# HT7463A.net
KiCad netlist of a schematic drawn in Altium Designer
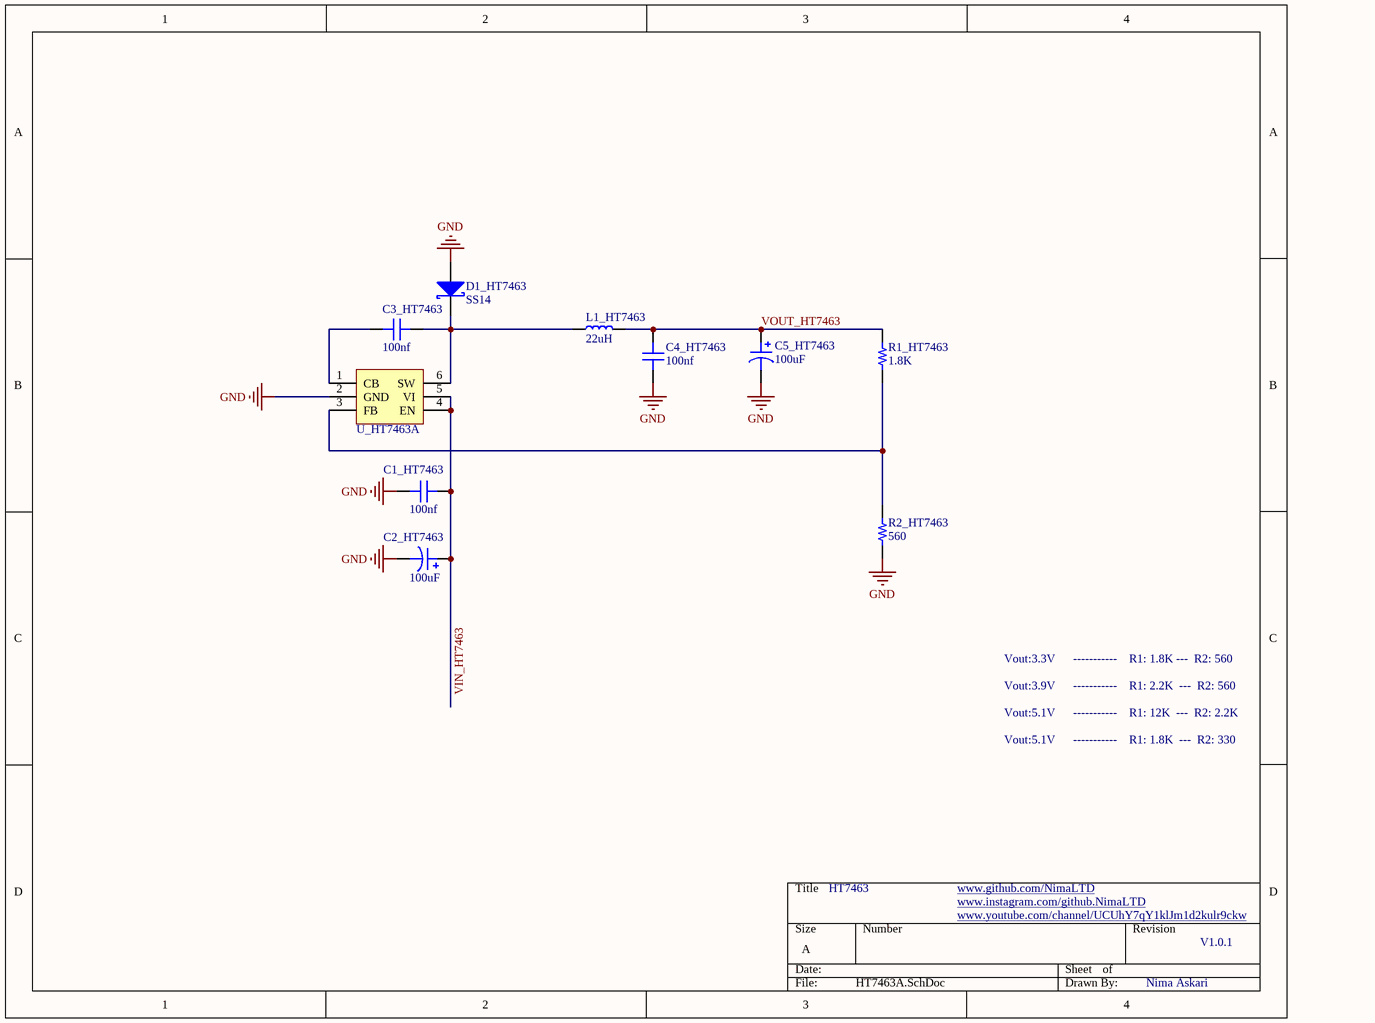
[diagram p0: HT7463A.SchDoc]

(export (version "E")
  (design (tool "Eeschema 10.0.6"))
  (components
    (comp (ref "C1_HT7463")
      (value "100nf")
      (footprint "CAP 1206")
      (description "SMT Capacitor")
      (libsource (lib "CAPACITOR") (part "Cap SMD 1206"))
    )
    (comp (ref "C2_HT7463")
      (value "100uF")
      (footprint "CAP AL SMD D6 H6")
      (description "SMT Polarised Capacitor")
      (libsource (lib "CAPACITOR") (part "Pol Cap SMD AL D6 H6"))
    )
    (comp (ref "C3_HT7463")
      (value "100nf")
      (footprint "CAP 0805")
      (description "SMT Capacitor")
      (libsource (lib "CAPACITOR") (part "Cap SMD 0805"))
    )
    (comp (ref "C4_HT7463")
      (value "100nf")
      (footprint "CAP 0805")
      (description "SMT Capacitor")
      (libsource (lib "CAPACITOR") (part "Cap SMD 0805"))
    )
    (comp (ref "C5_HT7463")
      (value "100uF")
      (footprint "CAP AL SMD D6 H6")
      (description "SMT Polarised Capacitor")
      (libsource (lib "") (part "Pol Cap SMD AL D6 H6_1"))
    )
    (comp (ref "D1_HT7463")
      (value "SS14 SMD")
      (footprint "DO214AC SMA")
      (description "1A Schottky")
      (fields (field (name "PARAMETER 1") "SS14"))
      (libsource (lib "DIODE") (part "SS14 SMD"))
    )
    (comp (ref "L1_HT7463")
      (value "22uH")
      (footprint "IND 5X5")
      (description "SMT Inductor")
      (fields (field (name "Comment") "Inductor SMD POWER 5X5mm"))
      (libsource (lib "INDUCTOR") (part "Inductor SMD POWER 5X5mm"))
    )
    (comp (ref "R1_HT7463")
      (value "1.8K")
      (footprint "RES 0805")
      (description "SMD Resistor")
      (libsource (lib "RESISTOR") (part "Res SMD 0805"))
    )
    (comp (ref "R2_HT7463")
      (value "560")
      (footprint "RES 0805")
      (description "SMD Resistor")
      (libsource (lib "RESISTOR") (part "Res SMD 0805"))
    )
    (comp (ref "U_HT7463A") (value "HT7463") (footprint "SOT23-6") (libsource (lib "IC") (part "HT7463")))
  )
  (nets
    (net (code "1") (name "/VIN_HT7463") (class "Default")
      (node (ref "C1_HT7463") (pin "2") (pinfunction "2_2") (pintype "passive"))
      (node (ref "C2_HT7463") (pin "1") (pinfunction "1_1") (pintype "passive"))
      (node (ref "U_HT7463A") (pin "4") (pinfunction "EN_4") (pintype "passive"))
      (node (ref "U_HT7463A") (pin "5") (pinfunction "VI_5") (pintype "passive"))
    )
    (net (code "2") (name "/VOUT_HT7463") (class "Default")
      (node (ref "C4_HT7463") (pin "2") (pinfunction "2_2") (pintype "passive"))
      (node (ref "C5_HT7463") (pin "1") (pinfunction "1_1") (pintype "passive"))
      (node (ref "L1_HT7463") (pin "2") (pinfunction "2_2") (pintype "passive"))
      (node (ref "R1_HT7463") (pin "2") (pinfunction "2_2") (pintype "passive"))
    )
    (net (code "3") (name "GND") (class "Default")
      (node (ref "C1_HT7463") (pin "1") (pinfunction "1_1") (pintype "passive"))
      (node (ref "C2_HT7463") (pin "2") (pinfunction "2_2") (pintype "passive"))
      (node (ref "C4_HT7463") (pin "1") (pinfunction "1_1") (pintype "passive"))
      (node (ref "C5_HT7463") (pin "2") (pinfunction "2_2") (pintype "passive"))
      (node (ref "D1_HT7463") (pin "1") (pinfunction "A_1") (pintype "passive"))
      (node (ref "R2_HT7463") (pin "1") (pinfunction "1_1") (pintype "passive"))
      (node (ref "U_HT7463A") (pin "2") (pinfunction "GND_2") (pintype "passive"))
    )
    (net (code "4") (name "Net-(D1_HT7463-K)") (class "Default")
      (node (ref "C3_HT7463") (pin "2") (pinfunction "2_2") (pintype "passive"))
      (node (ref "D1_HT7463") (pin "2") (pinfunction "K_2") (pintype "passive"))
      (node (ref "L1_HT7463") (pin "1") (pinfunction "1_1") (pintype "passive"))
      (node (ref "U_HT7463A") (pin "6") (pinfunction "SW_6") (pintype "passive"))
    )
    (net (code "5") (name "Net-(U_HT7463A-CB)") (class "Default")
      (node (ref "C3_HT7463") (pin "1") (pinfunction "1_1") (pintype "passive"))
      (node (ref "U_HT7463A") (pin "1") (pinfunction "CB_1") (pintype "passive"))
    )
    (net (code "6") (name "Net-(U_HT7463A-FB)") (class "Default")
      (node (ref "R1_HT7463") (pin "1") (pinfunction "1_1") (pintype "passive"))
      (node (ref "R2_HT7463") (pin "2") (pinfunction "2_2") (pintype "passive"))
      (node (ref "U_HT7463A") (pin "3") (pinfunction "FB_3") (pintype "passive"))
    )
  )
)
